# STM32LoRa.net
KiCad netlist of a schematic drawn in EAGLE
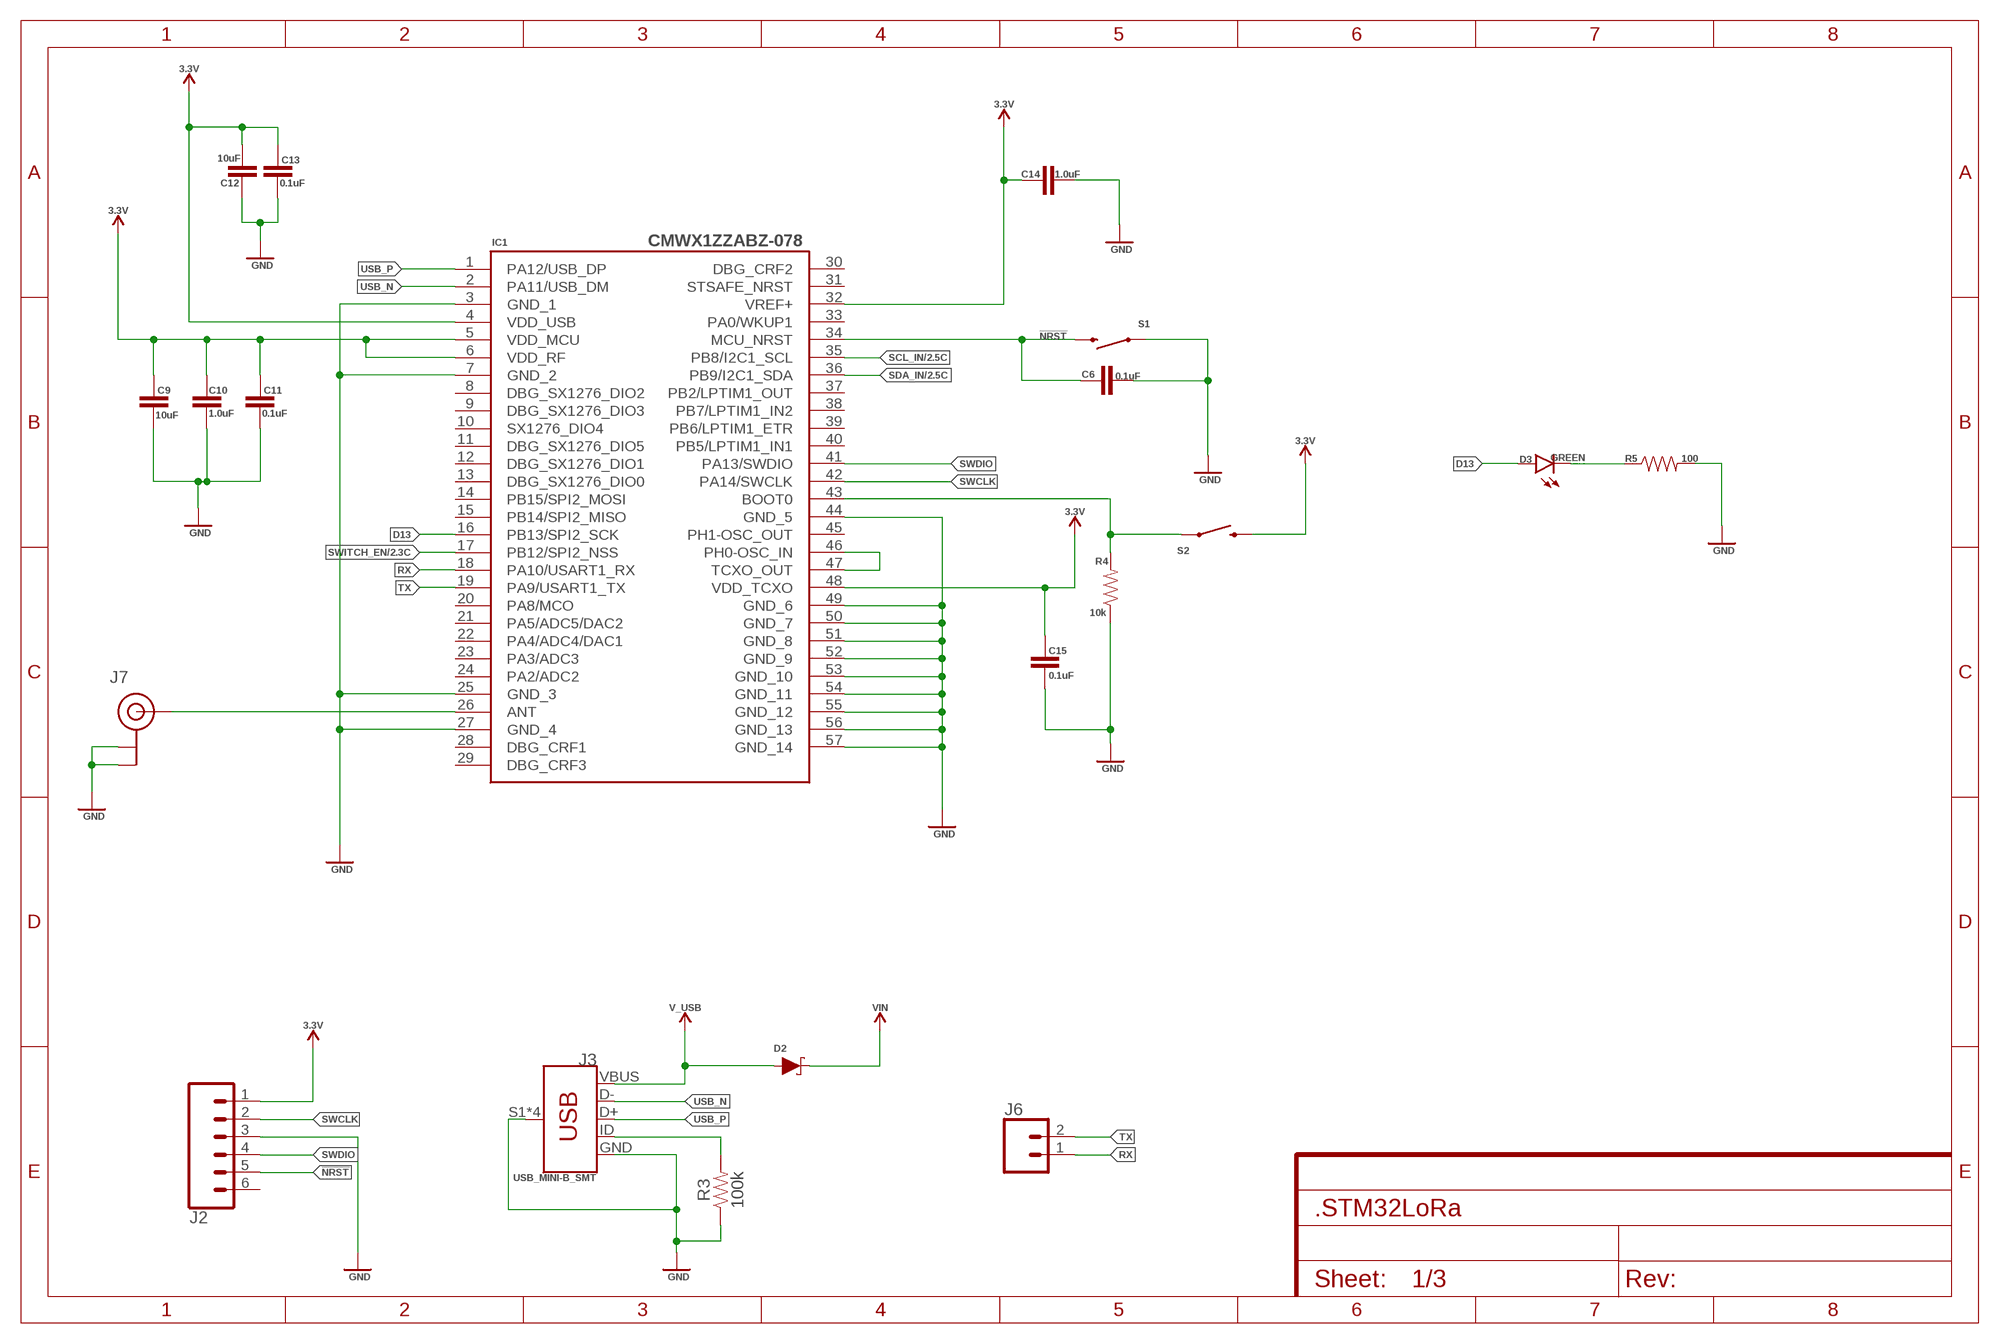
[diagram p0: schematic, sheet 1]
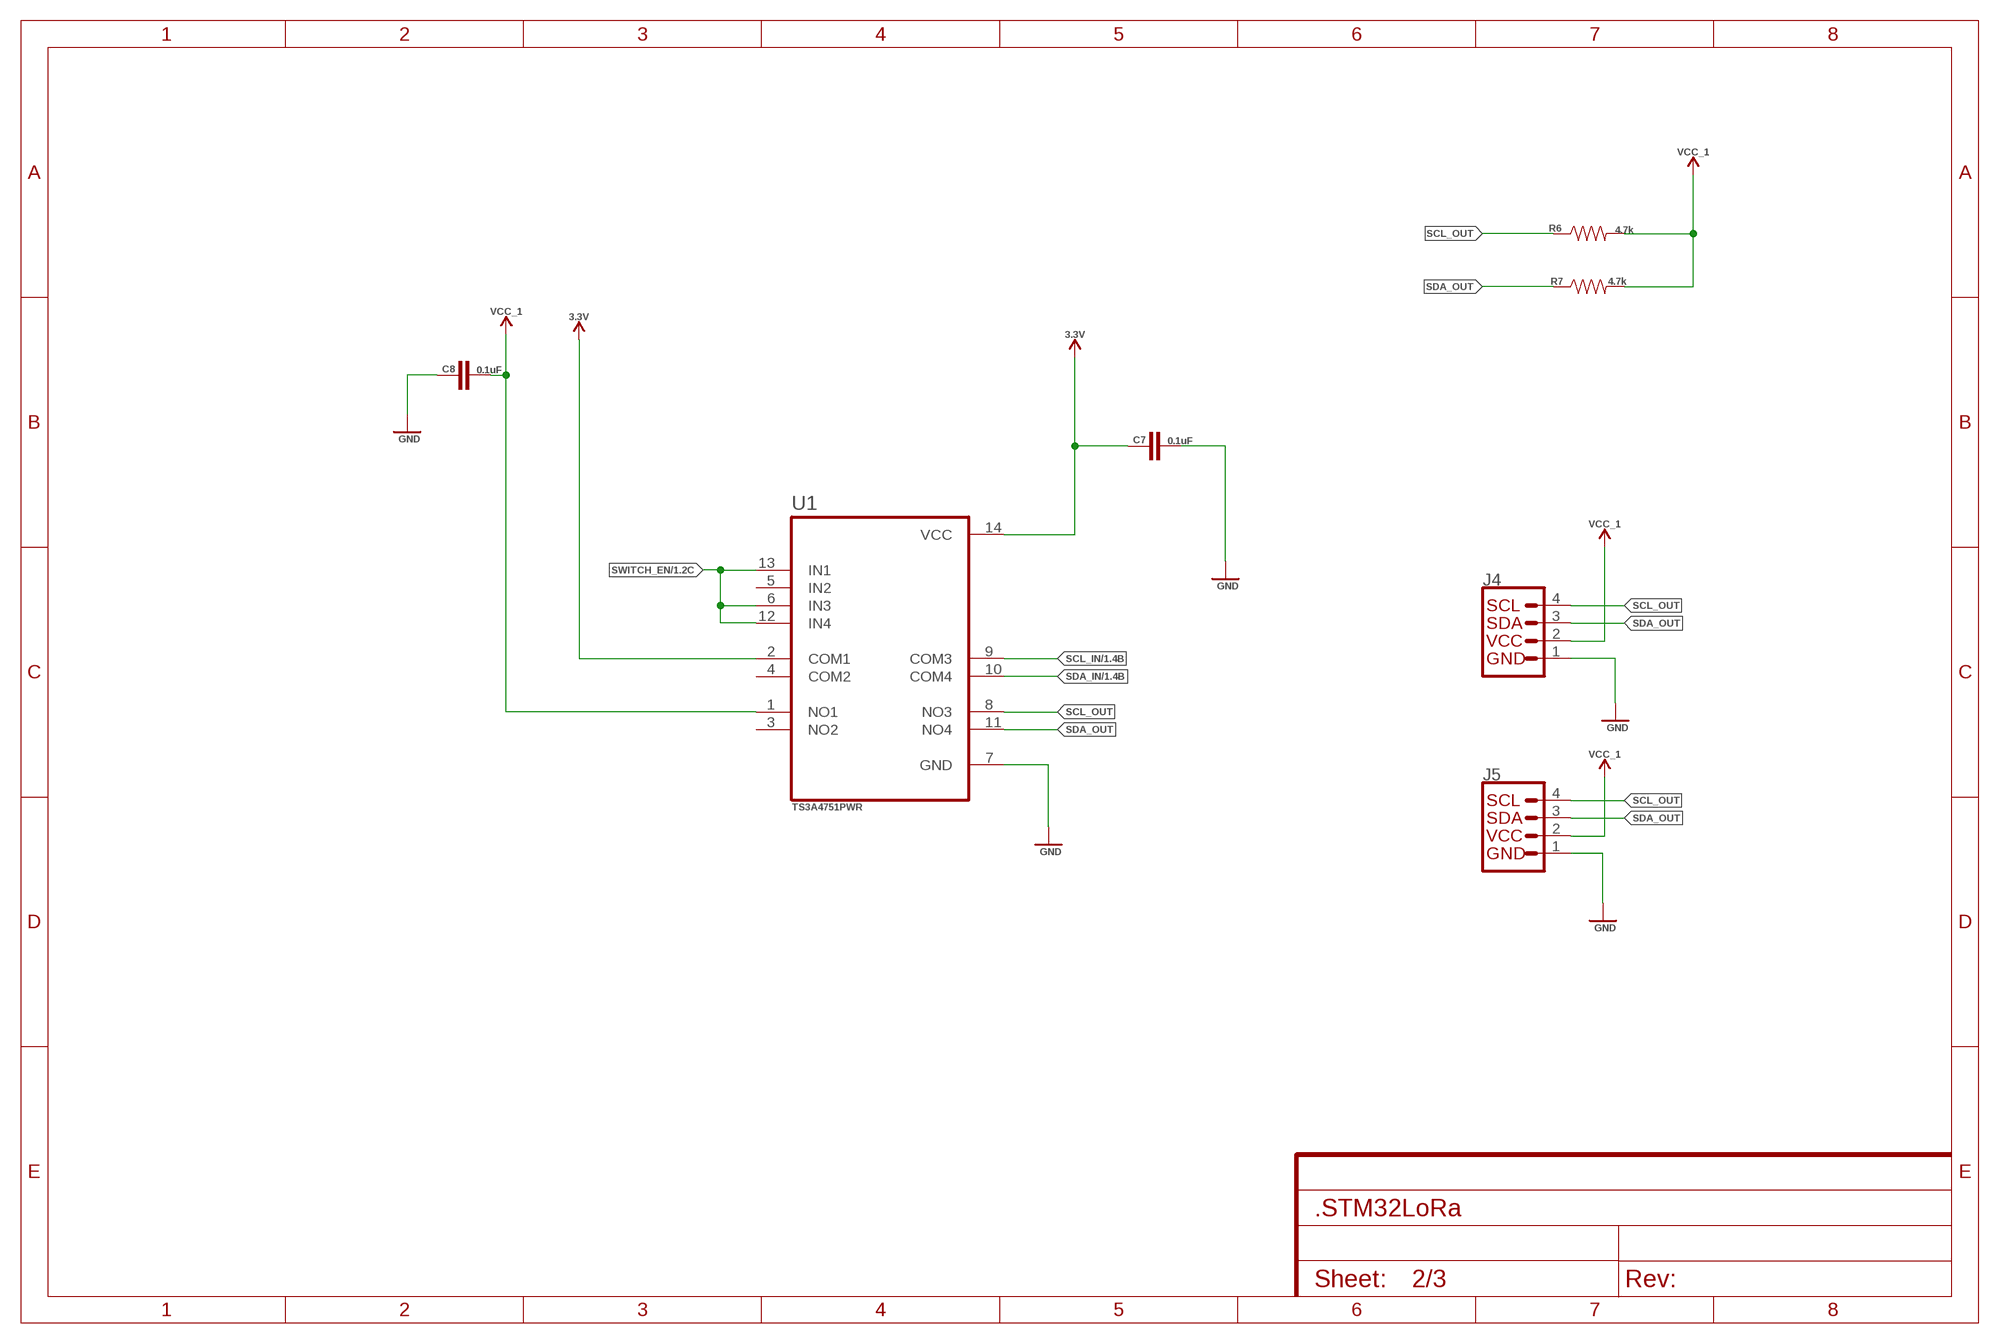
[diagram p1: schematic, sheet 2]
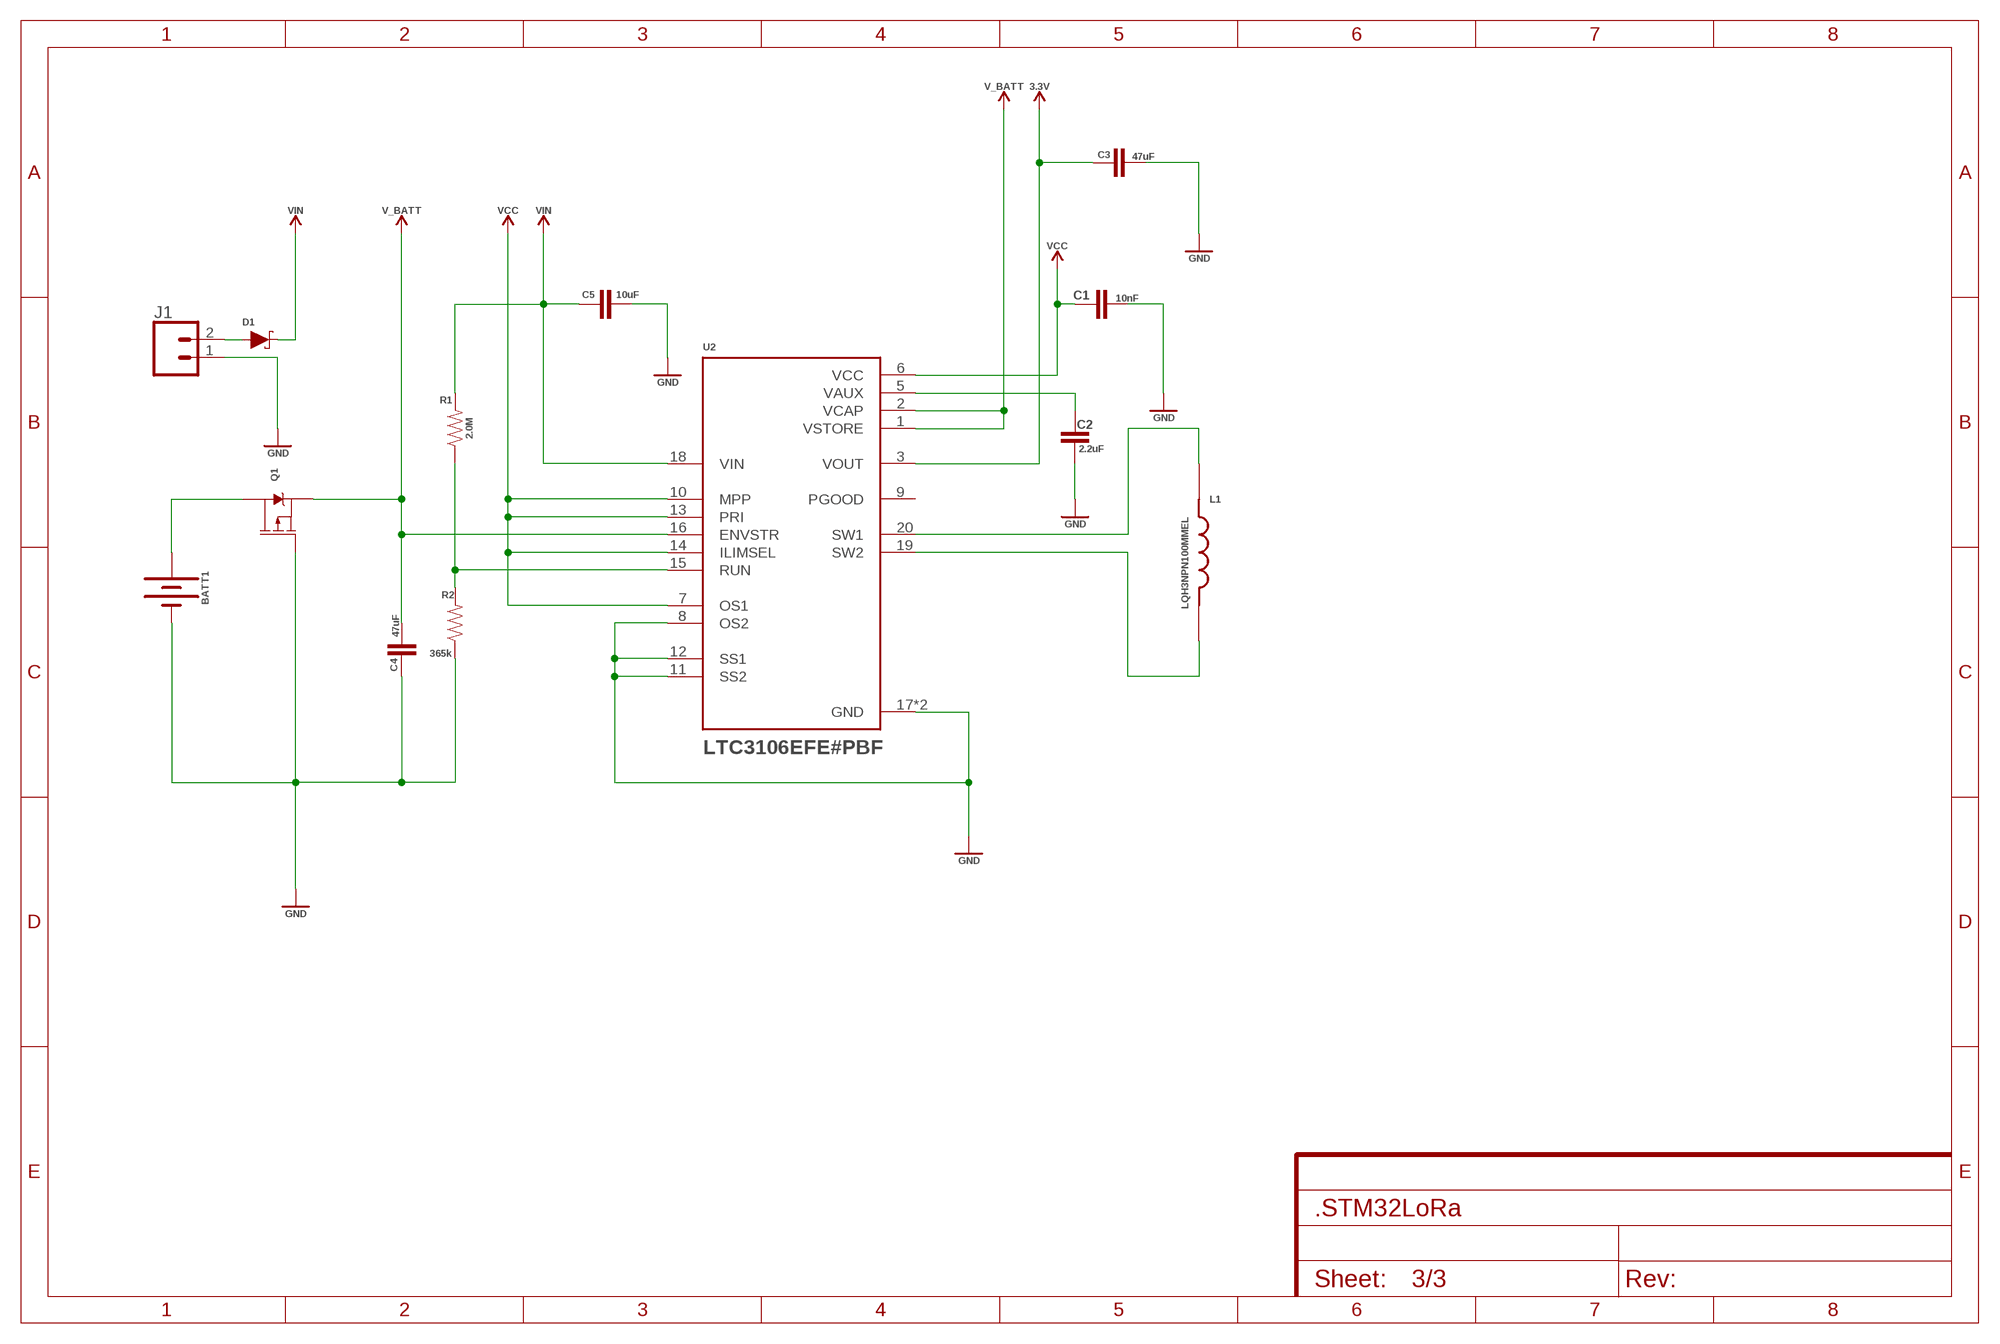
[diagram p2: schematic, sheet 3]

(export (version "E")
  (design (tool "Eeschema 10.0.6"))
  (components
    (comp (ref "C6")
      (value "0.1uF")
      (footprint "eagle-import:0603")
      (libsource (lib "eagle-import") (part "0.1UF-0603-25V-(+80/-20%)"))
    )
    (comp (ref "C9")
      (value "10uF")
      (footprint "eagle-import:0603")
      (libsource (lib "eagle-import") (part "10UF-0603-6.3V-20%"))
    )
    (comp (ref "C10")
      (value "1.0uF")
      (footprint "eagle-import:0603")
      (libsource (lib "eagle-import") (part "1.0UF-0603-16V-10%"))
    )
    (comp (ref "C11")
      (value "0.1uF")
      (footprint "eagle-import:0603")
      (libsource (lib "eagle-import") (part "0.1UF-0603-25V-(+80/-20%)"))
    )
    (comp (ref "C12")
      (value "10uF")
      (footprint "eagle-import:0603")
      (libsource (lib "eagle-import") (part "10UF-0603-6.3V-20%"))
    )
    (comp (ref "C13")
      (value "0.1uF")
      (footprint "eagle-import:0603")
      (libsource (lib "eagle-import") (part "0.1UF-0603-25V-(+80/-20%)"))
    )
    (comp (ref "C14")
      (value "1.0uF")
      (footprint "eagle-import:0603")
      (libsource (lib "eagle-import") (part "1.0UF-0603-16V-10%"))
    )
    (comp (ref "C15")
      (value "0.1uF")
      (footprint "eagle-import:0603")
      (libsource (lib "eagle-import") (part "0.1UF-0603-25V-(+80/-20%)"))
    )
    (comp (ref "D2")
      (value "120mA/40V/370mV")
      (footprint "eagle-import:SOD-523")
      (libsource (lib "eagle-import") (part "DIODE-SCHOTTKY-RB751S40"))
    )
    (comp (ref "D3")
      (value "GREEN")
      (footprint "eagle-import:LED-0603")
      (libsource (lib "eagle-import") (part "LED-GREEN0603"))
    )
    (comp (ref "IC1")
      (value "CMWX1ZZABZ-078")
      (footprint "eagle-import:CMWX1ZZABZ-078")
      (fields (field (name "MOUSER_PART_NUMBER") "81-CMWX1ZZABZ-078"))
      (libsource (lib "eagle-import") (part "CMWX1ZZABZ-078"))
    )
    (comp (ref "J2")
      (value "CONN_06LONGPADS")
      (footprint "eagle-import:1X06_LONGPADS")
      (libsource (lib "eagle-import") (part "CONN_06LONGPADS"))
    )
    (comp (ref "J3")
      (value "USB_MINI-B_SMT")
      (footprint "eagle-import:USB-MINIB")
      (libsource (lib "eagle-import") (part "USB_MINI-B_SMT"))
    )
    (comp (ref "J6")
      (value "CONN_02")
      (footprint "eagle-import:1X02")
      (libsource (lib "eagle-import") (part "CONN_02"))
    )
    (comp (ref "J7")
      (value "U.FL")
      (footprint "eagle-import:U.FL")
      (libsource (lib "eagle-import") (part "U.FL"))
    )
    (comp (ref "R3")
      (value "100k")
      (footprint "eagle-import:0603")
      (libsource (lib "eagle-import") (part "100KOHM-0603-1/10W-1%"))
    )
    (comp (ref "R4")
      (value "10k")
      (footprint "eagle-import:0603")
      (libsource (lib "eagle-import") (part "10KOHM-0603-1/10W-1%"))
    )
    (comp (ref "R5")
      (value "100")
      (footprint "eagle-import:0603")
      (libsource (lib "eagle-import") (part "100OHM-0603-1/4W-5%"))
    )
    (comp (ref "S1")
      (value "MOMENTARY-SWITCH-SPST-SMD-4.6X2.8MM")
      (footprint "eagle-import:TACTILE_SWITCH_SMD_4.6X2.8MM")
      (libsource (lib "eagle-import") (part "MOMENTARY-SWITCH-SPST-SMD-4.6X2.8MM"))
    )
    (comp (ref "S2")
      (value "MOMENTARY-SWITCH-SPST-SMD-4.6X2.8MM")
      (footprint "eagle-import:TACTILE_SWITCH_SMD_4.6X2.8MM")
      (libsource (lib "eagle-import") (part "MOMENTARY-SWITCH-SPST-SMD-4.6X2.8MM"))
    )
    (comp (ref "BATT1")
      (value "KEYSTONE_54KEYSTONE_2")
      (footprint "eagle-import:KEYSTONE_V2")
      (libsource (lib "eagle-import") (part "KEYSTONE_54KEYSTONE_2"))
    )
    (comp (ref "C1")
      (value "10nF")
      (footprint "eagle-import:0603")
      (libsource (lib "eagle-import") (part "10NF-0603-50V-10%"))
    )
    (comp (ref "C2")
      (value "2.2uF")
      (footprint "eagle-import:0603")
      (libsource (lib "eagle-import") (part "2.2UF-0603-10V-20%"))
    )
    (comp (ref "C3")
      (value "47uF")
      (footprint "eagle-import:0603")
      (libsource (lib "eagle-import") (part "4.7UF0603"))
    )
    (comp (ref "C4")
      (value "47uF")
      (footprint "eagle-import:0603")
      (libsource (lib "eagle-import") (part "4.7UF0603"))
    )
    (comp (ref "C5")
      (value "10uF")
      (footprint "eagle-import:0603")
      (libsource (lib "eagle-import") (part "10UF-0603-6.3V-20%"))
    )
    (comp (ref "D1")
      (value "120mA/40V/370mV")
      (footprint "eagle-import:SOD-523")
      (libsource (lib "eagle-import") (part "DIODE-SCHOTTKY-RB751S40"))
    )
    (comp (ref "J1")
      (value "CONN_023.5MM")
      (footprint "eagle-import:SCREWTERMINAL-3.5MM-2")
      (libsource (lib "eagle-import") (part "CONN_023.5MM"))
    )
    (comp (ref "L1")
      (value "LQH3NPN100MMEL")
      (footprint "eagle-import:IND_LQH3NPN100MMEL")
      (fields (field (name "DIGI-KEY_PART_NUMBER") "490-15945-1-ND") (field (name "MF") "Murata"))
      (libsource (lib "eagle-import") (part "LQH3NPN100MMEL"))
    )
    (comp (ref "Q1")
      (value "2.5A/30V/105mΩ")
      (footprint "eagle-import:SOT23-3")
      (libsource (lib "eagle-import") (part "MOSFET_PCH-DMG2307L"))
    )
    (comp (ref "R1")
      (value "2.0M")
      (footprint "eagle-import:0603")
      (libsource (lib "eagle-import") (part "2MOHMS-0603-1/10W-1%"))
    )
    (comp (ref "R2")
      (value "365k")
      (footprint "eagle-import:0603")
      (libsource (lib "eagle-import") (part "390KOHM-0603-1/10W-1%"))
    )
    (comp (ref "U2")
      (value "LTC3106EFE#PBF")
      (footprint "eagle-import:SOP65P640X120-21N")
      (fields (field (name "MF") "Analog Devices"))
      (libsource (lib "eagle-import") (part "LTC3106EFE#PBF"))
    )
    (comp (ref "C7")
      (value "0.1uF")
      (footprint "eagle-import:0603")
      (libsource (lib "eagle-import") (part "0.1UF-0603-25V-(+80/-20%)"))
    )
    (comp (ref "C8")
      (value "0.1uF")
      (footprint "eagle-import:0603")
      (libsource (lib "eagle-import") (part "0.1UF-0603-25V-(+80/-20%)"))
    )
    (comp (ref "J4")
      (value "Qwiic Right Angle")
      (footprint "eagle-import:1X04_1MM_RA")
      (libsource (lib "eagle-import") (part "I2C_STANDARDQWIIC"))
    )
    (comp (ref "J5")
      (value "I2C_STANDARD")
      (footprint "eagle-import:1X04")
      (libsource (lib "eagle-import") (part "I2C_STANDARD"))
    )
    (comp (ref "R6")
      (value "4.7k")
      (footprint "eagle-import:0603")
      (libsource (lib "eagle-import") (part "4.7KOHM-0603-1/10W-1%"))
    )
    (comp (ref "R7")
      (value "4.7k")
      (footprint "eagle-import:0603")
      (libsource (lib "eagle-import") (part "4.7KOHM-0603-1/10W-1%"))
    )
    (comp (ref "U1")
      (value "TS3A4751PWR")
      (footprint "eagle-import:SOP65P640X120-14N")
      (fields (field (name "DIGI-KEY_PART_NUMBER") "296-20700-1-ND") (field (name "MF") "Texas Instruments"))
      (libsource (lib "eagle-import") (part "TS3A4751PWR"))
    )
  )
  (nets
    (net (code "1") (name "3.3V") (class "Default")
      (node (ref "C10") (pin "1") (pinfunction "1_1") (pintype "passive"))
      (node (ref "C11") (pin "1") (pinfunction "1_1") (pintype "passive"))
      (node (ref "C12") (pin "2") (pinfunction "2_2") (pintype "passive"))
      (node (ref "C13") (pin "1") (pinfunction "1_1") (pintype "passive"))
      (node (ref "C14") (pin "1") (pinfunction "1_1") (pintype "passive"))
      (node (ref "C15") (pin "2") (pinfunction "2_2") (pintype "passive"))
      (node (ref "C3") (pin "1") (pinfunction "1_1") (pintype "passive"))
      (node (ref "C7") (pin "1") (pinfunction "1_1") (pintype "passive"))
      (node (ref "C9") (pin "1") (pinfunction "1_1") (pintype "passive"))
      (node (ref "IC1") (pin "32") (pinfunction "VREF+_32") (pintype "bidirectional"))
      (node (ref "IC1") (pin "4") (pinfunction "VDD_USB_4") (pintype "bidirectional"))
      (node (ref "IC1") (pin "48") (pinfunction "VDD_TCXO_48") (pintype "bidirectional"))
      (node (ref "IC1") (pin "5") (pinfunction "VDD_MCU_5") (pintype "bidirectional"))
      (node (ref "IC1") (pin "6") (pinfunction "VDD_RF_6") (pintype "bidirectional"))
      (node (ref "J2") (pin "1") (pinfunction "1_1") (pintype "passive"))
      (node (ref "S2") (pin "3") (pinfunction "2_3") (pintype "passive"))
      (node (ref "S2") (pin "4") (pinfunction "2_4") (pintype "passive"))
      (node (ref "U1") (pin "14") (pinfunction "VCC_14") (pintype "power_in"))
      (node (ref "U1") (pin "2") (pinfunction "COM1_2") (pintype "bidirectional"))
      (node (ref "U2") (pin "3") (pinfunction "VOUT_3") (pintype "output"))
    )
    (net (code "2") (name "D13") (class "Default")
      (node (ref "D3") (pin "A") (pinfunction "A_A") (pintype "passive"))
      (node (ref "IC1") (pin "16") (pinfunction "PB13/SPI2_SCK_16") (pintype "bidirectional"))
    )
    (net (code "3") (name "GND") (class "Default")
      (node (ref "BATT1") (pin "P$4") (pinfunction "-_P$4") (pintype "power_in"))
      (node (ref "BATT1") (pin "P$5") (pinfunction "-_P$5") (pintype "power_in"))
      (node (ref "BATT1") (pin "P$6") (pinfunction "-_P$6") (pintype "power_in"))
      (node (ref "C1") (pin "2") (pinfunction "2_2") (pintype "passive"))
      (node (ref "C10") (pin "2") (pinfunction "2_2") (pintype "passive"))
      (node (ref "C11") (pin "2") (pinfunction "2_2") (pintype "passive"))
      (node (ref "C12") (pin "1") (pinfunction "1_1") (pintype "passive"))
      (node (ref "C13") (pin "2") (pinfunction "2_2") (pintype "passive"))
      (node (ref "C14") (pin "2") (pinfunction "2_2") (pintype "passive"))
      (node (ref "C15") (pin "1") (pinfunction "1_1") (pintype "passive"))
      (node (ref "C2") (pin "2") (pinfunction "2_2") (pintype "passive"))
      (node (ref "C3") (pin "2") (pinfunction "2_2") (pintype "passive"))
      (node (ref "C4") (pin "1") (pinfunction "1_1") (pintype "passive"))
      (node (ref "C5") (pin "2") (pinfunction "2_2") (pintype "passive"))
      (node (ref "C6") (pin "2") (pinfunction "2_2") (pintype "passive"))
      (node (ref "C7") (pin "2") (pinfunction "2_2") (pintype "passive"))
      (node (ref "C8") (pin "1") (pinfunction "1_1") (pintype "passive"))
      (node (ref "C9") (pin "2") (pinfunction "2_2") (pintype "passive"))
      (node (ref "IC1") (pin "25") (pinfunction "GND_3_25") (pintype "bidirectional"))
      (node (ref "IC1") (pin "27") (pinfunction "GND_4_27") (pintype "bidirectional"))
      (node (ref "IC1") (pin "3") (pinfunction "GND_1_3") (pintype "bidirectional"))
      (node (ref "IC1") (pin "44") (pinfunction "GND_5_44") (pintype "bidirectional"))
      (node (ref "IC1") (pin "49") (pinfunction "GND_6_49") (pintype "bidirectional"))
      (node (ref "IC1") (pin "50") (pinfunction "GND_7_50") (pintype "bidirectional"))
      (node (ref "IC1") (pin "51") (pinfunction "GND_8_51") (pintype "bidirectional"))
      (node (ref "IC1") (pin "52") (pinfunction "GND_9_52") (pintype "bidirectional"))
      (node (ref "IC1") (pin "53") (pinfunction "GND_10_53") (pintype "bidirectional"))
      (node (ref "IC1") (pin "54") (pinfunction "GND_11_54") (pintype "bidirectional"))
      (node (ref "IC1") (pin "55") (pinfunction "GND_12_55") (pintype "bidirectional"))
      (node (ref "IC1") (pin "56") (pinfunction "GND_13_56") (pintype "bidirectional"))
      (node (ref "IC1") (pin "57") (pinfunction "GND_14_57") (pintype "bidirectional"))
      (node (ref "IC1") (pin "7") (pinfunction "GND_2_7") (pintype "bidirectional"))
      (node (ref "J1") (pin "1") (pinfunction "1_1") (pintype "passive"))
      (node (ref "J2") (pin "3") (pinfunction "3_3") (pintype "passive"))
      (node (ref "J3") (pin "GND") (pinfunction "GND_GND") (pintype "power_in"))
      (node (ref "J3") (pin "S1") (pinfunction "SHIELD_S1") (pintype "bidirectional"))
      (node (ref "J3") (pin "S2") (pinfunction "SHIELD_S2") (pintype "bidirectional"))
      (node (ref "J3") (pin "S3") (pinfunction "SHIELD_S3") (pintype "bidirectional"))
      (node (ref "J3") (pin "S4") (pinfunction "SHIELD_S4") (pintype "bidirectional"))
      (node (ref "J4") (pin "1") (pinfunction "1_1") (pintype "power_in"))
      (node (ref "J5") (pin "1") (pinfunction "1_1") (pintype "power_in"))
      (node (ref "J7") (pin "1") (pinfunction "GND_1") (pintype "bidirectional"))
      (node (ref "J7") (pin "2") (pinfunction "GND_2") (pintype "bidirectional"))
      (node (ref "Q1") (pin "1") (pinfunction "G_1") (pintype "bidirectional"))
      (node (ref "R2") (pin "1") (pinfunction "1_1") (pintype "passive"))
      (node (ref "R3") (pin "1") (pinfunction "1_1") (pintype "passive"))
      (node (ref "R4") (pin "1") (pinfunction "1_1") (pintype "passive"))
      (node (ref "R5") (pin "2") (pinfunction "2_2") (pintype "passive"))
      (node (ref "S1") (pin "1") (pinfunction "1_1") (pintype "passive"))
      (node (ref "S1") (pin "2") (pinfunction "1_2") (pintype "passive"))
      (node (ref "U1") (pin "7") (pinfunction "GND_7") (pintype "power_in"))
      (node (ref "U2") (pin "11") (pinfunction "SS2_11") (pintype "input"))
      (node (ref "U2") (pin "12") (pinfunction "SS1_12") (pintype "input"))
      (node (ref "U2") (pin "17") (pinfunction "GND_17") (pintype "power_in"))
      (node (ref "U2") (pin "21") (pinfunction "GND_21") (pintype "power_in"))
      (node (ref "U2") (pin "8") (pinfunction "OS2_8") (pintype "input"))
    )
    (net (code "4") (name "Net-(D1-PadA)") (class "Default")
      (node (ref "D1") (pin "A") (pinfunction "A_A") (pintype "passive"))
      (node (ref "J1") (pin "2") (pinfunction "2_2") (pintype "passive"))
    )
    (net (code "5") (name "Net-(D3-PadC)") (class "Default")
      (node (ref "D3") (pin "C") (pinfunction "C_C") (pintype "passive"))
      (node (ref "R5") (pin "1") (pinfunction "1_1") (pintype "passive"))
    )
    (net (code "6") (name "Net-(IC1-ANT)") (class "Default")
      (node (ref "IC1") (pin "26") (pinfunction "ANT_26") (pintype "bidirectional"))
      (node (ref "J7") (pin "FEED") (pinfunction "SIGNAL_FEED") (pintype "bidirectional"))
    )
    (net (code "7") (name "Net-(IC1-BOOT0)") (class "Default")
      (node (ref "IC1") (pin "43") (pinfunction "BOOT0_43") (pintype "bidirectional"))
      (node (ref "R4") (pin "2") (pinfunction "2_2") (pintype "passive"))
      (node (ref "S2") (pin "1") (pinfunction "1_1") (pintype "passive"))
      (node (ref "S2") (pin "2") (pinfunction "1_2") (pintype "passive"))
    )
    (net (code "8") (name "Net-(IC1-PH0-OSC_IN)") (class "Default")
      (node (ref "IC1") (pin "46") (pinfunction "PH0-OSC_IN_46") (pintype "bidirectional"))
      (node (ref "IC1") (pin "47") (pinfunction "TCXO_OUT_47") (pintype "bidirectional"))
    )
    (net (code "9") (name "Net-(J3-PadID)") (class "Default")
      (node (ref "J3") (pin "ID") (pinfunction "ID_ID") (pintype "bidirectional"))
      (node (ref "R3") (pin "2") (pinfunction "2_2") (pintype "passive"))
    )
    (net (code "10") (name "Net-(Q1-D)") (class "Default")
      (node (ref "BATT1") (pin "P$1") (pinfunction "+_P$1") (pintype "power_in"))
      (node (ref "BATT1") (pin "P$2") (pinfunction "+_P$2") (pintype "power_in"))
      (node (ref "BATT1") (pin "P$3") (pinfunction "+_P$3") (pintype "power_in"))
      (node (ref "Q1") (pin "3") (pinfunction "D_3") (pintype "bidirectional"))
    )
    (net (code "11") (name "Net-(U2-RUN)") (class "Default")
      (node (ref "R1") (pin "1") (pinfunction "1_1") (pintype "passive"))
      (node (ref "R2") (pin "2") (pinfunction "2_2") (pintype "passive"))
      (node (ref "U2") (pin "15") (pinfunction "RUN_15") (pintype "input"))
    )
    (net (code "12") (name "Net-(U2-SW1)") (class "Default")
      (node (ref "L1") (pin "1") (pinfunction "1_1") (pintype "passive"))
      (node (ref "U2") (pin "20") (pinfunction "SW1_20") (pintype "passive"))
    )
    (net (code "13") (name "Net-(U2-SW2)") (class "Default")
      (node (ref "L1") (pin "2") (pinfunction "2_2") (pintype "passive"))
      (node (ref "U2") (pin "19") (pinfunction "SW2_19") (pintype "passive"))
    )
    (net (code "14") (name "Net-(U2-VAUX)") (class "Default")
      (node (ref "C2") (pin "1") (pinfunction "1_1") (pintype "passive"))
      (node (ref "U2") (pin "5") (pinfunction "VAUX_5") (pintype "power_in"))
    )
    (net (code "15") (name "RX") (class "Default")
      (node (ref "IC1") (pin "18") (pinfunction "PA10/USART1_RX_18") (pintype "bidirectional"))
      (node (ref "J6") (pin "1") (pinfunction "1_1") (pintype "passive"))
    )
    (net (code "16") (name "SCL_IN") (class "Default")
      (node (ref "IC1") (pin "35") (pinfunction "PB8/I2C1_SCL_35") (pintype "bidirectional"))
      (node (ref "U1") (pin "9") (pinfunction "COM3_9") (pintype "bidirectional"))
    )
    (net (code "17") (name "SCL_OUT") (class "Default")
      (node (ref "J4") (pin "4") (pinfunction "4_4") (pintype "passive"))
      (node (ref "J5") (pin "4") (pinfunction "4_4") (pintype "passive"))
      (node (ref "R6") (pin "1") (pinfunction "1_1") (pintype "passive"))
      (node (ref "U1") (pin "8") (pinfunction "NO3_8") (pintype "bidirectional"))
    )
    (net (code "18") (name "SDA_IN") (class "Default")
      (node (ref "IC1") (pin "36") (pinfunction "PB9/I2C1_SDA_36") (pintype "bidirectional"))
      (node (ref "U1") (pin "10") (pinfunction "COM4_10") (pintype "bidirectional"))
    )
    (net (code "19") (name "SDA_OUT") (class "Default")
      (node (ref "J4") (pin "3") (pinfunction "3_3") (pintype "passive"))
      (node (ref "J5") (pin "3") (pinfunction "3_3") (pintype "passive"))
      (node (ref "R7") (pin "1") (pinfunction "1_1") (pintype "passive"))
      (node (ref "U1") (pin "11") (pinfunction "NO4_11") (pintype "bidirectional"))
    )
    (net (code "20") (name "SWCLK") (class "Default")
      (node (ref "IC1") (pin "42") (pinfunction "PA14/SWCLK_42") (pintype "bidirectional"))
      (node (ref "J2") (pin "2") (pinfunction "2_2") (pintype "passive"))
    )
    (net (code "21") (name "SWDIO") (class "Default")
      (node (ref "IC1") (pin "41") (pinfunction "PA13/SWDIO_41") (pintype "bidirectional"))
      (node (ref "J2") (pin "4") (pinfunction "4_4") (pintype "passive"))
    )
    (net (code "22") (name "SWITCH_EN") (class "Default")
      (node (ref "IC1") (pin "17") (pinfunction "PB12/SPI2_NSS_17") (pintype "bidirectional"))
      (node (ref "U1") (pin "12") (pinfunction "IN4_12") (pintype "input"))
      (node (ref "U1") (pin "13") (pinfunction "IN1_13") (pintype "input"))
      (node (ref "U1") (pin "6") (pinfunction "IN3_6") (pintype "input"))
    )
    (net (code "23") (name "TX") (class "Default")
      (node (ref "IC1") (pin "19") (pinfunction "PA9/USART1_TX_19") (pintype "bidirectional"))
      (node (ref "J6") (pin "2") (pinfunction "2_2") (pintype "passive"))
    )
    (net (code "24") (name "USB_N") (class "Default")
      (node (ref "IC1") (pin "2") (pinfunction "PA11/USB_DM_2") (pintype "bidirectional"))
      (node (ref "J3") (pin "D-") (pinfunction "D-_D-") (pintype "bidirectional"))
    )
    (net (code "25") (name "USB_P") (class "Default")
      (node (ref "IC1") (pin "1") (pinfunction "PA12/USB_DP_1") (pintype "bidirectional"))
      (node (ref "J3") (pin "D+") (pinfunction "D+_D+") (pintype "bidirectional"))
    )
    (net (code "26") (name "VCC") (class "Default")
      (node (ref "C1") (pin "1") (pinfunction "1_1") (pintype "passive"))
      (node (ref "U2") (pin "10") (pinfunction "MPP_10") (pintype "input"))
      (node (ref "U2") (pin "13") (pinfunction "PRI_13") (pintype "input"))
      (node (ref "U2") (pin "14") (pinfunction "ILIMSEL_14") (pintype "input"))
      (node (ref "U2") (pin "6") (pinfunction "VCC_6") (pintype "power_in"))
      (node (ref "U2") (pin "7") (pinfunction "OS1_7") (pintype "input"))
    )
    (net (code "27") (name "VCC_1") (class "Default")
      (node (ref "C8") (pin "2") (pinfunction "2_2") (pintype "passive"))
      (node (ref "J4") (pin "2") (pinfunction "2_2") (pintype "power_in"))
      (node (ref "J5") (pin "2") (pinfunction "2_2") (pintype "power_in"))
      (node (ref "R6") (pin "2") (pinfunction "2_2") (pintype "passive"))
      (node (ref "R7") (pin "2") (pinfunction "2_2") (pintype "passive"))
      (node (ref "U1") (pin "1") (pinfunction "NO1_1") (pintype "bidirectional"))
    )
    (net (code "28") (name "VIN") (class "Default")
      (node (ref "C5") (pin "1") (pinfunction "1_1") (pintype "passive"))
      (node (ref "D1") (pin "C") (pinfunction "C_C") (pintype "passive"))
      (node (ref "D2") (pin "C") (pinfunction "C_C") (pintype "passive"))
      (node (ref "R1") (pin "2") (pinfunction "2_2") (pintype "passive"))
      (node (ref "U2") (pin "18") (pinfunction "VIN_18") (pintype "input"))
    )
    (net (code "29") (name "V_BATT") (class "Default")
      (node (ref "C4") (pin "2") (pinfunction "2_2") (pintype "passive"))
      (node (ref "Q1") (pin "2") (pinfunction "S_2") (pintype "bidirectional"))
      (node (ref "U2") (pin "1") (pinfunction "VSTORE_1") (pintype "power_in"))
      (node (ref "U2") (pin "16") (pinfunction "ENVSTR_16") (pintype "input"))
      (node (ref "U2") (pin "2") (pinfunction "VCAP_2") (pintype "power_in"))
    )
    (net (code "30") (name "V_USB") (class "Default")
      (node (ref "D2") (pin "A") (pinfunction "A_A") (pintype "passive"))
      (node (ref "J3") (pin "VBUS") (pinfunction "VBUS_VBUS") (pintype "power_in"))
    )
    (net (code "31") (name "unconnected-(IC1-DBG_CRF1-Pad28)") (class "Default")
      (node (ref "IC1") (pin "28") (pinfunction "DBG_CRF1_28") (pintype "bidirectional"))
    )
    (net (code "32") (name "unconnected-(IC1-DBG_CRF2-Pad30)") (class "Default")
      (node (ref "IC1") (pin "30") (pinfunction "DBG_CRF2_30") (pintype "bidirectional"))
    )
    (net (code "33") (name "unconnected-(IC1-DBG_CRF3-Pad29)") (class "Default")
      (node (ref "IC1") (pin "29") (pinfunction "DBG_CRF3_29") (pintype "bidirectional"))
    )
    (net (code "34") (name "unconnected-(IC1-DBG_SX1276_DIO0-Pad13)") (class "Default")
      (node (ref "IC1") (pin "13") (pinfunction "DBG_SX1276_DIO0_13") (pintype "bidirectional"))
    )
    (net (code "35") (name "unconnected-(IC1-DBG_SX1276_DIO1-Pad12)") (class "Default")
      (node (ref "IC1") (pin "12") (pinfunction "DBG_SX1276_DIO1_12") (pintype "bidirectional"))
    )
    (net (code "36") (name "unconnected-(IC1-DBG_SX1276_DIO2-Pad8)") (class "Default")
      (node (ref "IC1") (pin "8") (pinfunction "DBG_SX1276_DIO2_8") (pintype "bidirectional"))
    )
    (net (code "37") (name "unconnected-(IC1-DBG_SX1276_DIO3-Pad9)") (class "Default")
      (node (ref "IC1") (pin "9") (pinfunction "DBG_SX1276_DIO3_9") (pintype "bidirectional"))
    )
    (net (code "38") (name "unconnected-(IC1-DBG_SX1276_DIO5-Pad11)") (class "Default")
      (node (ref "IC1") (pin "11") (pinfunction "DBG_SX1276_DIO5_11") (pintype "bidirectional"))
    )
    (net (code "39") (name "unconnected-(IC1-PA0{slash}WKUP1-Pad33)") (class "Default")
      (node (ref "IC1") (pin "33") (pinfunction "PA0/WKUP1_33") (pintype "bidirectional"))
    )
    (net (code "40") (name "unconnected-(IC1-PA2{slash}ADC2-Pad24)") (class "Default")
      (node (ref "IC1") (pin "24") (pinfunction "PA2/ADC2_24") (pintype "bidirectional"))
    )
    (net (code "41") (name "unconnected-(IC1-PA3{slash}ADC3-Pad23)") (class "Default")
      (node (ref "IC1") (pin "23") (pinfunction "PA3/ADC3_23") (pintype "bidirectional"))
    )
    (net (code "42") (name "unconnected-(IC1-PA4{slash}ADC4{slash}DAC1-Pad22)") (class "Default")
      (node (ref "IC1") (pin "22") (pinfunction "PA4/ADC4/DAC1_22") (pintype "bidirectional"))
    )
    (net (code "43") (name "unconnected-(IC1-PA5{slash}ADC5{slash}DAC2-Pad21)") (class "Default")
      (node (ref "IC1") (pin "21") (pinfunction "PA5/ADC5/DAC2_21") (pintype "bidirectional"))
    )
    (net (code "44") (name "unconnected-(IC1-PA8{slash}MCO-Pad20)") (class "Default")
      (node (ref "IC1") (pin "20") (pinfunction "PA8/MCO_20") (pintype "bidirectional"))
    )
    (net (code "45") (name "unconnected-(IC1-PB2{slash}LPTIM1_OUT-Pad37)") (class "Default")
      (node (ref "IC1") (pin "37") (pinfunction "PB2/LPTIM1_OUT_37") (pintype "bidirectional"))
    )
    (net (code "46") (name "unconnected-(IC1-PB5{slash}LPTIM1_IN1-Pad40)") (class "Default")
      (node (ref "IC1") (pin "40") (pinfunction "PB5/LPTIM1_IN1_40") (pintype "bidirectional"))
    )
    (net (code "47") (name "unconnected-(IC1-PB6{slash}LPTIM1_ETR-Pad39)") (class "Default")
      (node (ref "IC1") (pin "39") (pinfunction "PB6/LPTIM1_ETR_39") (pintype "bidirectional"))
    )
    (net (code "48") (name "unconnected-(IC1-PB7{slash}LPTIM1_IN2-Pad38)") (class "Default")
      (node (ref "IC1") (pin "38") (pinfunction "PB7/LPTIM1_IN2_38") (pintype "bidirectional"))
    )
    (net (code "49") (name "unconnected-(IC1-PB14{slash}SPI2_MISO-Pad15)") (class "Default")
      (node (ref "IC1") (pin "15") (pinfunction "PB14/SPI2_MISO_15") (pintype "bidirectional"))
    )
    (net (code "50") (name "unconnected-(IC1-PB15{slash}SPI2_MOSI-Pad14)") (class "Default")
      (node (ref "IC1") (pin "14") (pinfunction "PB15/SPI2_MOSI_14") (pintype "bidirectional"))
    )
    (net (code "51") (name "unconnected-(IC1-PH1-OSC_OUT-Pad45)") (class "Default")
      (node (ref "IC1") (pin "45") (pinfunction "PH1-OSC_OUT_45") (pintype "bidirectional"))
    )
    (net (code "52") (name "unconnected-(IC1-STSAFE_NRST-Pad31)") (class "Default")
      (node (ref "IC1") (pin "31") (pinfunction "STSAFE_NRST_31") (pintype "bidirectional"))
    )
    (net (code "53") (name "unconnected-(IC1-SX1276_DIO4-Pad10)") (class "Default")
      (node (ref "IC1") (pin "10") (pinfunction "SX1276_DIO4_10") (pintype "bidirectional"))
    )
    (net (code "54") (name "unconnected-(J2-Pad6)") (class "Default")
      (node (ref "J2") (pin "6") (pinfunction "6_6") (pintype "passive"))
    )
    (net (code "55") (name "unconnected-(U1-COM2-Pad4)") (class "Default")
      (node (ref "U1") (pin "4") (pinfunction "COM2_4") (pintype "bidirectional"))
    )
    (net (code "56") (name "unconnected-(U1-IN2-Pad5)") (class "Default")
      (node (ref "U1") (pin "5") (pinfunction "IN2_5") (pintype "input"))
    )
    (net (code "57") (name "unconnected-(U1-NO2-Pad3)") (class "Default")
      (node (ref "U1") (pin "3") (pinfunction "NO2_3") (pintype "bidirectional"))
    )
    (net (code "58") (name "unconnected-(U2-PGOOD-Pad9)") (class "Default")
      (node (ref "U2") (pin "9") (pinfunction "PGOOD_9") (pintype "output"))
    )
    (net (code "59") (name "~{NRST}") (class "Default")
      (node (ref "C6") (pin "1") (pinfunction "1_1") (pintype "passive"))
      (node (ref "IC1") (pin "34") (pinfunction "MCU_NRST_34") (pintype "bidirectional"))
      (node (ref "J2") (pin "5") (pinfunction "5_5") (pintype "passive"))
      (node (ref "S1") (pin "3") (pinfunction "2_3") (pintype "passive"))
      (node (ref "S1") (pin "4") (pinfunction "2_4") (pintype "passive"))
    )
  )
)
